# untitled.net
KiCad netlist of a schematic drawn in EAGLE
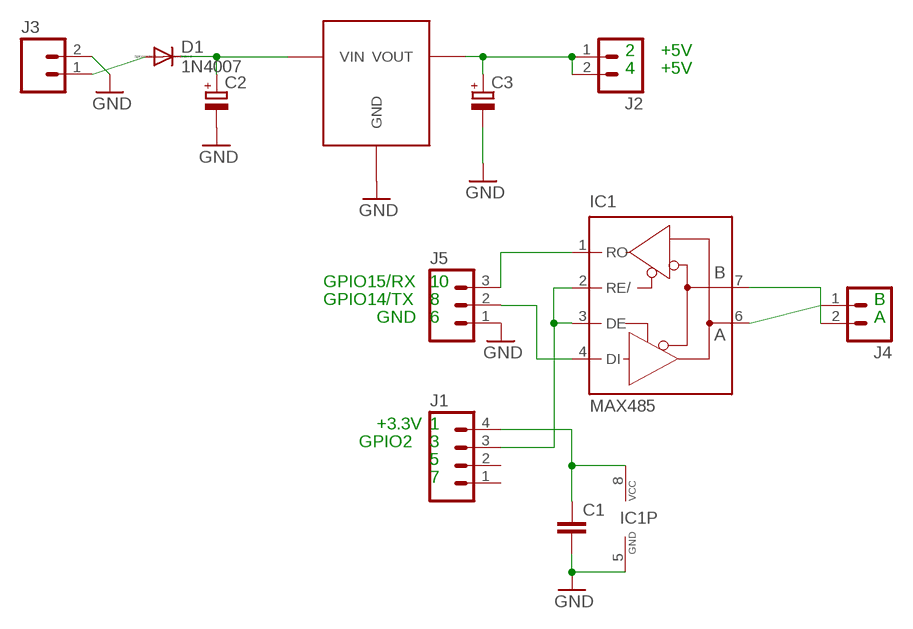
[diagram p0: schematic, sheet 1]

(export (version "E")
  (design (tool "Eeschema 10.0.6"))
  (components
    (comp (ref "C1")
      (value "C-EU050-025X075")
      (footprint "eagle-import:C050-025X075")
      (libsource (lib "eagle-import") (part "C-EU050-025X075"))
    )
    (comp (ref "C2")
      (value "CPOL-EUE2-4")
      (footprint "eagle-import:E2-4")
      (libsource (lib "eagle-import") (part "CPOL-EUE2-4"))
    )
    (comp (ref "C3")
      (value "CPOL-EUE2-4")
      (footprint "eagle-import:E2-4")
      (libsource (lib "eagle-import") (part "CPOL-EUE2-4"))
    )
    (comp (ref "D1")
      (value "1N4007")
      (footprint "eagle-import:DO41-10")
      (libsource (lib "eagle-import") (part "1N4007"))
    )
    (comp (ref "IC1")
      (value "MAX485")
      (footprint "eagle-import:DIL08")
      (fields (field (name "MPN") "MAX481CPA+"))
      (libsource (lib "eagle-import") (part "MAX485"))
    )
    (comp (ref "J1")
      (value "M04")
      (footprint "eagle-import:1X04")
      (libsource (lib "eagle-import") (part "M04"))
    )
    (comp (ref "J2")
      (value "M02")
      (footprint "eagle-import:1X02")
      (libsource (lib "eagle-import") (part "M02"))
    )
    (comp (ref "J3")
      (value "M02-SCREW-3.5MM3.5MM")
      (footprint "eagle-import:SCREWTERMINAL-3.5MM-2")
      (libsource (lib "eagle-import") (part "M02-SCREW-3.5MM3.5MM"))
    )
    (comp (ref "J4")
      (value "M02-SCREW-3.5MM3.5MM")
      (footprint "eagle-import:SCREWTERMINAL-3.5MM-2")
      (libsource (lib "eagle-import") (part "M02-SCREW-3.5MM3.5MM"))
    )
    (comp (ref "J5")
      (value "M03")
      (footprint "eagle-import:1X03")
      (libsource (lib "eagle-import") (part "M03"))
    )
    (comp (ref "U$1")
      (value "DSUN-MP1584")
      (footprint "eagle-import:DSUN-MP1584")
      (libsource (lib "eagle-import") (part "DSUN-MP1584"))
    )
  )
  (nets
    (net (code "1") (name "GND") (class "Default")
      (node (ref "C1") (pin "2") (pinfunction "2_2") (pintype "passive"))
      (node (ref "C2") (pin "-") (pinfunction "-_-") (pintype "passive"))
      (node (ref "C3") (pin "-") (pinfunction "-_-") (pintype "passive"))
      (node (ref "IC1") (pin "5") (pinfunction "GND_5") (pintype "power_in"))
      (node (ref "J3") (pin "2") (pinfunction "2_2") (pintype "passive"))
      (node (ref "J5") (pin "1") (pinfunction "1_1") (pintype "passive"))
      (node (ref "U$1") (pin "GND1") (pinfunction "GND_GND1") (pintype "bidirectional"))
    )
    (net (code "2") (name "Net-(D1-PadA)") (class "Default")
      (node (ref "D1") (pin "A") (pinfunction "A_A") (pintype "passive"))
      (node (ref "J3") (pin "1") (pinfunction "1_1") (pintype "passive"))
    )
    (net (code "3") (name "Net-(IC1A-A)") (class "Default")
      (node (ref "IC1") (pin "6") (pinfunction "A_6") (pintype "passive"))
      (node (ref "J4") (pin "1") (pinfunction "1_1") (pintype "passive"))
    )
    (net (code "4") (name "Net-(IC1A-B)") (class "Default")
      (node (ref "IC1") (pin "7") (pinfunction "B_7") (pintype "passive"))
      (node (ref "J4") (pin "2") (pinfunction "2_2") (pintype "passive"))
    )
    (net (code "5") (name "Net-(IC1A-DE)") (class "Default")
      (node (ref "IC1") (pin "2") (pinfunction "RE/_2") (pintype "input"))
      (node (ref "IC1") (pin "3") (pinfunction "DE_3") (pintype "input"))
      (node (ref "J1") (pin "3") (pinfunction "3_3") (pintype "passive"))
    )
    (net (code "6") (name "Net-(IC1A-DI)") (class "Default")
      (node (ref "IC1") (pin "4") (pinfunction "DI_4") (pintype "input"))
      (node (ref "J5") (pin "2") (pinfunction "2_2") (pintype "passive"))
    )
    (net (code "7") (name "Net-(IC1A-RO)") (class "Default")
      (node (ref "IC1") (pin "1") (pinfunction "RO_1") (pintype "output"))
      (node (ref "J5") (pin "3") (pinfunction "3_3") (pintype "passive"))
    )
    (net (code "8") (name "Net-(IC1B-VCC)") (class "Default")
      (node (ref "C1") (pin "1") (pinfunction "1_1") (pintype "passive"))
      (node (ref "IC1") (pin "8") (pinfunction "VCC_8") (pintype "power_in"))
      (node (ref "J1") (pin "4") (pinfunction "4_4") (pintype "passive"))
    )
    (net (code "9") (name "Net-(U$1-VIN)") (class "Default")
      (node (ref "C2") (pin "+") (pinfunction "+_+") (pintype "passive"))
      (node (ref "D1") (pin "C") (pinfunction "C_C") (pintype "passive"))
      (node (ref "U$1") (pin "IN1") (pinfunction "VIN_IN1") (pintype "power_in"))
    )
    (net (code "10") (name "Net-(U$1-VOUT)") (class "Default")
      (node (ref "C3") (pin "+") (pinfunction "+_+") (pintype "passive"))
      (node (ref "J2") (pin "1") (pinfunction "1_1") (pintype "passive"))
      (node (ref "J2") (pin "2") (pinfunction "2_2") (pintype "passive"))
      (node (ref "U$1") (pin "OUT1") (pinfunction "VOUT_OUT1") (pintype "bidirectional"))
    )
    (net (code "11") (name "unconnected-(J1-Pad1)") (class "Default")
      (node (ref "J1") (pin "1") (pinfunction "1_1") (pintype "passive"))
    )
    (net (code "12") (name "unconnected-(J1-Pad2)") (class "Default")
      (node (ref "J1") (pin "2") (pinfunction "2_2") (pintype "passive"))
    )
  )
)
